# MECHWARFARE_BOARD.net
KiCad netlist of a schematic drawn in EAGLE
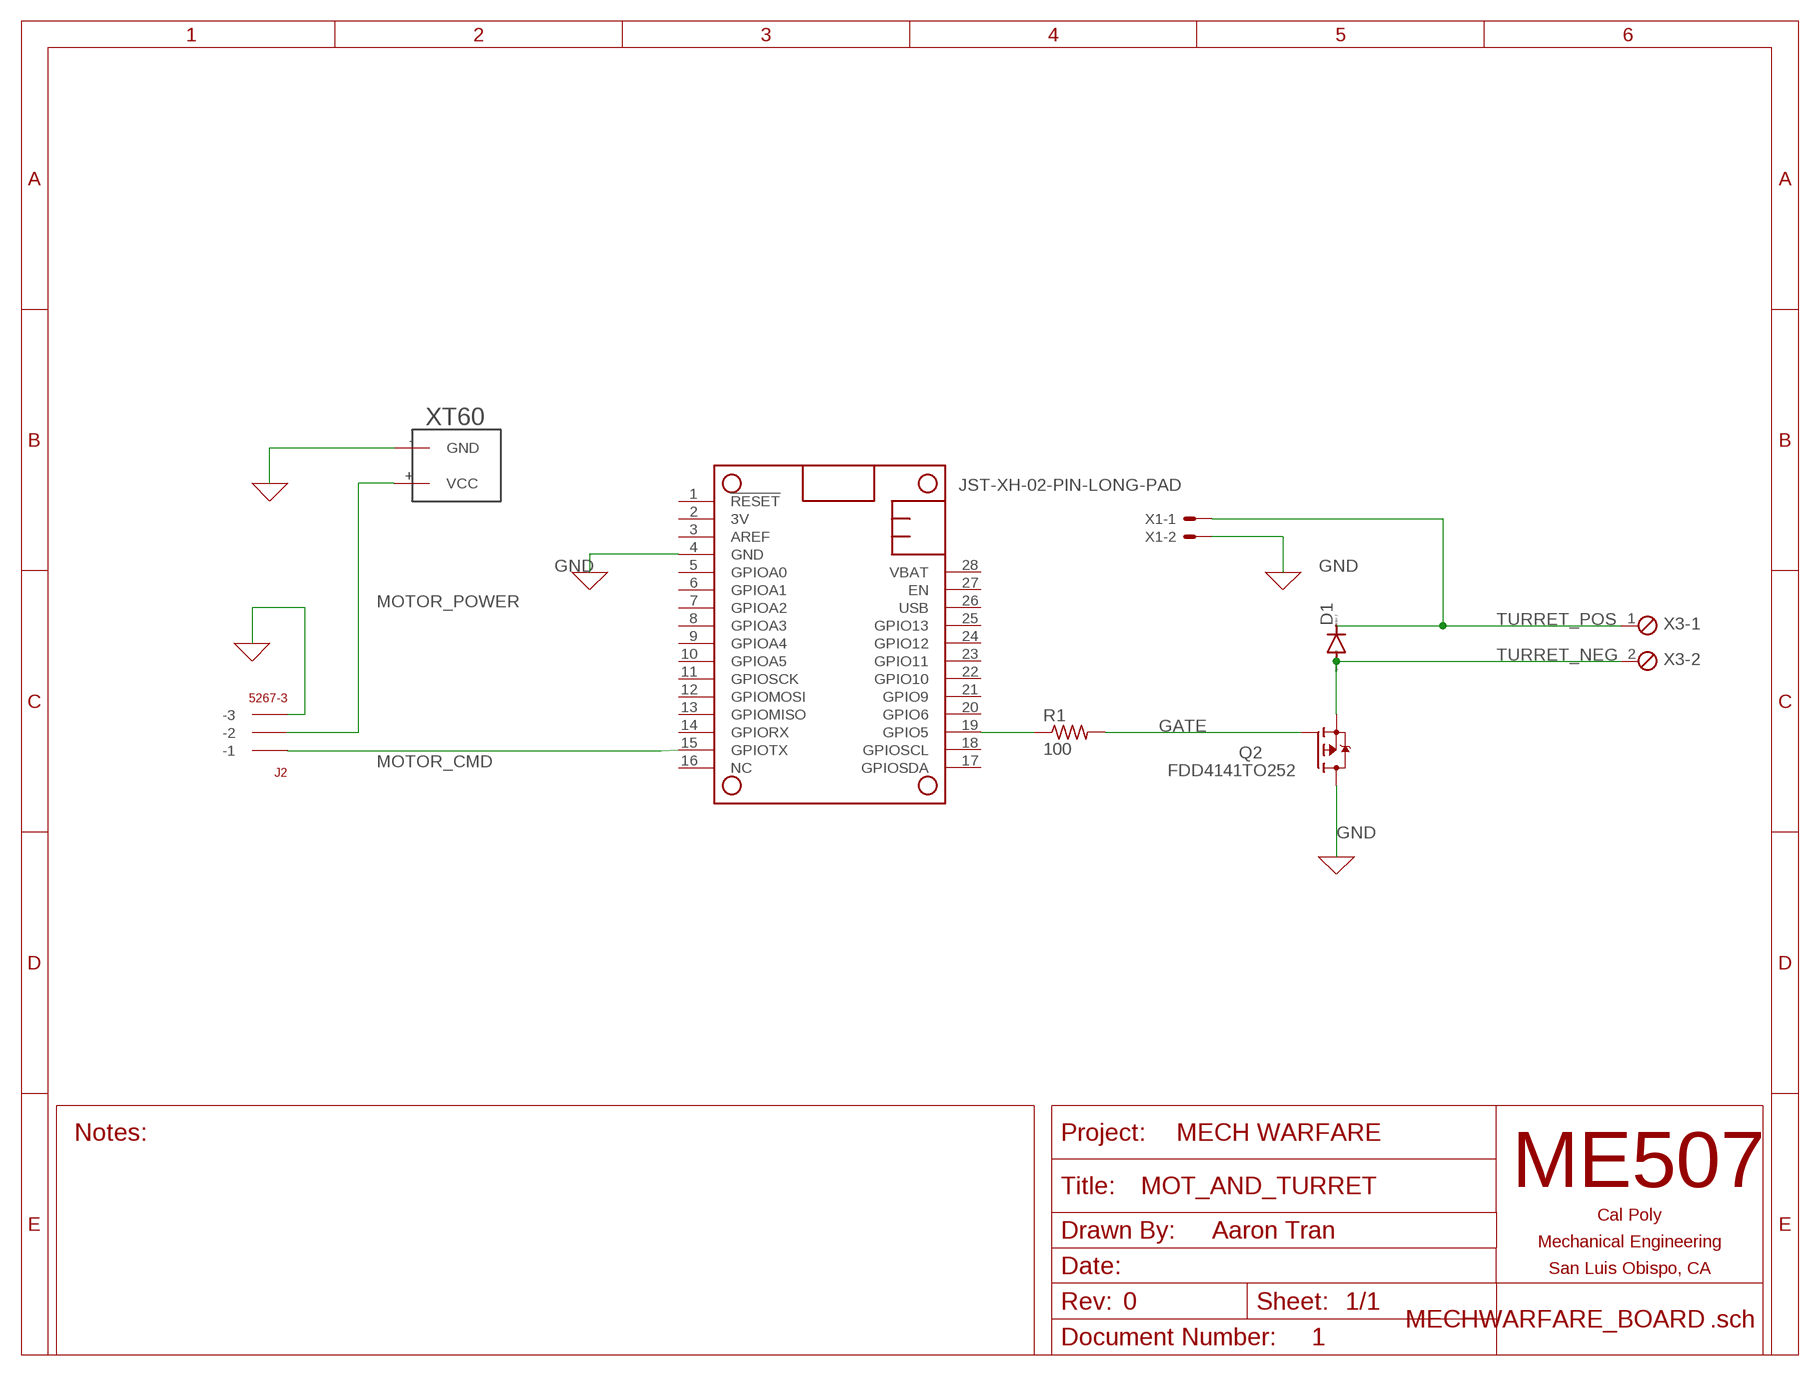
[diagram p0: schematic, sheet 1]

(export (version "E")
  (design (tool "Eeschema 10.0.6"))
  (components
    (comp (ref "D1")
      (value "DIODE-DO-214AC")
      (footprint "eagle-import:DO-214AC")
      (libsource (lib "eagle-import") (part "DIODE-DO-214AC"))
    )
    (comp (ref "J2")
      (value "5267-3")
      (footprint "eagle-import:5267-3")
      (libsource (lib "eagle-import") (part "5267-3"))
    )
    (comp (ref "MS2")
      (value "FEATHERWINGEXTENDED_BOTH_ENDS")
      (footprint "eagle-import:FEATHERWING")
      (libsource (lib "eagle-import") (part "FEATHERWINGEXTENDED_BOTH_ENDS"))
    )
    (comp (ref "Q2")
      (value "FDD4141TO252")
      (footprint "eagle-import:TO252")
      (libsource (lib "eagle-import") (part "FDD4141TO252"))
    )
    (comp (ref "R1")
      (value "100")
      (footprint "eagle-import:R0805")
      (libsource (lib "eagle-import") (part "R-US_R0805"))
    )
    (comp (ref "U$1")
      (value "XT60")
      (footprint "eagle-import:XT60")
      (libsource (lib "eagle-import") (part "XT60"))
    )
    (comp (ref "X1")
      (value "JST-XH-02-PIN-LONG-PAD")
      (footprint "eagle-import:JST-XH-02-PACKAGE-LONG-PAD")
      (libsource (lib "eagle-import") (part "JST-XH-02-PIN-LONG-PAD"))
    )
    (comp (ref "X3")
      (value "SCREWTERM_2P_254")
      (footprint "eagle-import:2POL254")
      (libsource (lib "eagle-import") (part "SCREWTERM_2P_254"))
    )
  )
  (nets
    (net (code "1") (name "/3V") (class "Default")
      (node (ref "MS2") (pin "2") (pinfunction "3V_2") (pintype "power_in"))
    )
    (net (code "2") (name "/GATE") (class "Default")
      (node (ref "Q2") (pin "1") (pinfunction "G_1") (pintype "passive"))
      (node (ref "R1") (pin "2") (pinfunction "2_2") (pintype "passive"))
    )
    (net (code "3") (name "/MOTOR_CMD") (class "Default")
      (node (ref "J2") (pin "P$1") (pinfunction "-1_P$1") (pintype "bidirectional"))
      (node (ref "MS2") (pin "15") (pinfunction "GPIOTX_15") (pintype "bidirectional"))
    )
    (net (code "4") (name "/MOTOR_POWER") (class "Default")
      (node (ref "J2") (pin "P$2") (pinfunction "-2_P$2") (pintype "bidirectional"))
      (node (ref "U$1") (pin "+") (pinfunction "VCC_+") (pintype "bidirectional"))
    )
    (net (code "5") (name "/TURRET_NEG") (class "Default")
      (node (ref "D1") (pin "A") (pinfunction "A_A") (pintype "passive"))
      (node (ref "Q2") (pin "2") (pinfunction "S_2") (pintype "passive"))
      (node (ref "X3") (pin "2") (pinfunction "1_2") (pintype "passive"))
    )
    (net (code "6") (name "/TURRET_POS") (class "Default")
      (node (ref "D1") (pin "C") (pinfunction "C_C") (pintype "passive"))
      (node (ref "X1") (pin "1") (pinfunction "S_1") (pintype "passive"))
      (node (ref "X3") (pin "1") (pinfunction "1_1") (pintype "passive"))
    )
    (net (code "7") (name "/USB") (class "Default")
      (node (ref "MS2") (pin "26") (pinfunction "USB_26") (pintype "power_in"))
    )
    (net (code "8") (name "/VBAT") (class "Default")
      (node (ref "MS2") (pin "28") (pinfunction "VBAT_28") (pintype "power_in"))
    )
    (net (code "9") (name "GND") (class "Default")
      (node (ref "J2") (pin "P$3") (pinfunction "-3_P$3") (pintype "bidirectional"))
      (node (ref "MS2") (pin "4") (pinfunction "GND_4") (pintype "power_in"))
      (node (ref "Q2") (pin "3") (pinfunction "D_3") (pintype "passive"))
      (node (ref "U$1") (pin "-") (pinfunction "GND_-") (pintype "bidirectional"))
      (node (ref "X1") (pin "2") (pinfunction "S_2") (pintype "passive"))
    )
    (net (code "10") (name "Net-(MS2-GPIO5)") (class "Default")
      (node (ref "MS2") (pin "19") (pinfunction "GPIO5_19") (pintype "bidirectional"))
      (node (ref "R1") (pin "1") (pinfunction "1_1") (pintype "passive"))
    )
    (net (code "11") (name "unconnected-(MS2-AREF-Pad3)") (class "Default")
      (node (ref "MS2") (pin "3") (pinfunction "AREF_3") (pintype "passive"))
    )
    (net (code "12") (name "unconnected-(MS2-EN-Pad27)") (class "Default")
      (node (ref "MS2") (pin "27") (pinfunction "EN_27") (pintype "passive"))
    )
    (net (code "13") (name "unconnected-(MS2-GPIO6-Pad20)") (class "Default")
      (node (ref "MS2") (pin "20") (pinfunction "GPIO6_20") (pintype "bidirectional"))
    )
    (net (code "14") (name "unconnected-(MS2-GPIO9-Pad21)") (class "Default")
      (node (ref "MS2") (pin "21") (pinfunction "GPIO9_21") (pintype "bidirectional"))
    )
    (net (code "15") (name "unconnected-(MS2-GPIO10-Pad22)") (class "Default")
      (node (ref "MS2") (pin "22") (pinfunction "GPIO10_22") (pintype "bidirectional"))
    )
    (net (code "16") (name "unconnected-(MS2-GPIO11-Pad23)") (class "Default")
      (node (ref "MS2") (pin "23") (pinfunction "GPIO11_23") (pintype "bidirectional"))
    )
    (net (code "17") (name "unconnected-(MS2-GPIO12-Pad24)") (class "Default")
      (node (ref "MS2") (pin "24") (pinfunction "GPIO12_24") (pintype "bidirectional"))
    )
    (net (code "18") (name "unconnected-(MS2-GPIO13-Pad25)") (class "Default")
      (node (ref "MS2") (pin "25") (pinfunction "GPIO13_25") (pintype "bidirectional"))
    )
    (net (code "19") (name "unconnected-(MS2-GPIOA0-Pad5)") (class "Default")
      (node (ref "MS2") (pin "5") (pinfunction "GPIOA0_5") (pintype "bidirectional"))
    )
    (net (code "20") (name "unconnected-(MS2-GPIOA1-Pad6)") (class "Default")
      (node (ref "MS2") (pin "6") (pinfunction "GPIOA1_6") (pintype "bidirectional"))
    )
    (net (code "21") (name "unconnected-(MS2-GPIOA2-Pad7)") (class "Default")
      (node (ref "MS2") (pin "7") (pinfunction "GPIOA2_7") (pintype "bidirectional"))
    )
    (net (code "22") (name "unconnected-(MS2-GPIOA3-Pad8)") (class "Default")
      (node (ref "MS2") (pin "8") (pinfunction "GPIOA3_8") (pintype "bidirectional"))
    )
    (net (code "23") (name "unconnected-(MS2-GPIOA4-Pad9)") (class "Default")
      (node (ref "MS2") (pin "9") (pinfunction "GPIOA4_9") (pintype "bidirectional"))
    )
    (net (code "24") (name "unconnected-(MS2-GPIOA5-Pad10)") (class "Default")
      (node (ref "MS2") (pin "10") (pinfunction "GPIOA5_10") (pintype "bidirectional"))
    )
    (net (code "25") (name "unconnected-(MS2-GPIOMISO-Pad13)") (class "Default")
      (node (ref "MS2") (pin "13") (pinfunction "GPIOMISO_13") (pintype "bidirectional"))
    )
    (net (code "26") (name "unconnected-(MS2-GPIOMOSI-Pad12)") (class "Default")
      (node (ref "MS2") (pin "12") (pinfunction "GPIOMOSI_12") (pintype "bidirectional"))
    )
    (net (code "27") (name "unconnected-(MS2-GPIORX-Pad14)") (class "Default")
      (node (ref "MS2") (pin "14") (pinfunction "GPIORX_14") (pintype "bidirectional"))
    )
    (net (code "28") (name "unconnected-(MS2-GPIOSCK-Pad11)") (class "Default")
      (node (ref "MS2") (pin "11") (pinfunction "GPIOSCK_11") (pintype "bidirectional"))
    )
    (net (code "29") (name "unconnected-(MS2-GPIOSCL-Pad18)") (class "Default")
      (node (ref "MS2") (pin "18") (pinfunction "GPIOSCL_18") (pintype "bidirectional"))
    )
    (net (code "30") (name "unconnected-(MS2-GPIOSDA-Pad17)") (class "Default")
      (node (ref "MS2") (pin "17") (pinfunction "GPIOSDA_17") (pintype "bidirectional"))
    )
    (net (code "31") (name "unconnected-(MS2-NC-Pad16)") (class "Default")
      (node (ref "MS2") (pin "16") (pinfunction "NC_16") (pintype "passive"))
    )
    (net (code "32") (name "unconnected-(MS2-~{RESET}-Pad1)") (class "Default")
      (node (ref "MS2") (pin "1") (pinfunction "~{RESET}_1") (pintype "input"))
    )
  )
)
